# 10_-_FPGA_IO_BANK_3A.net
KiCad netlist of a schematic drawn in Altium Designer
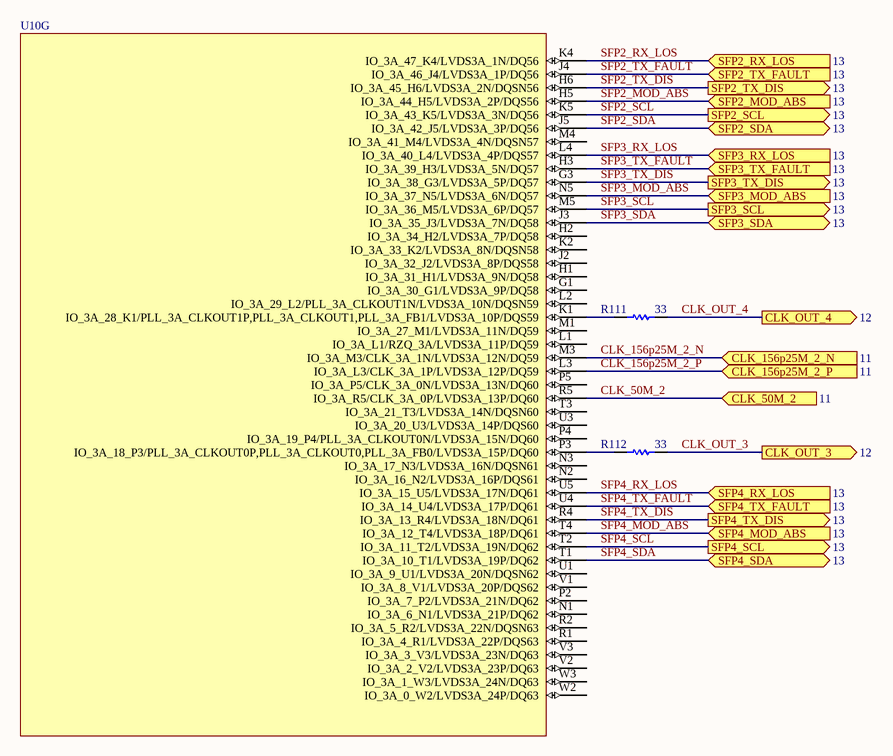
[diagram p0: [10] - FPGA IO BANK 3A.SchDoc]

(export (version "E")
  (design (tool "Eeschema 10.0.6"))
  (components
    (comp (ref "R111")
      (value "33")
      (footprint "0402_R")
      (description "SMD Resistor")
      (fields (field (name "TOLERANCE") "5%"))
      (libsource (lib "Passive Components") (part "Res SMD"))
    )
    (comp (ref "R112")
      (value "33")
      (footprint "0402_R")
      (description "SMD Resistor")
      (fields (field (name "TOLERANCE") "5%"))
      (libsource (lib "Passive Components") (part "Res SMD"))
    )
    (comp (ref "U10")
      (value "10AX016 F27")
      (footprint "FBGA672")
      (libsource (lib "Project_schlib") (part "10AX016"))
    )
  )
  (nets
    (net (code "1") (name "/CLK_50M_2") (class "Default")
      (node (ref "U10") (pin "R5") (pinfunction "IO_3A_R5/CLK_3A_0P/LVDS3A_13P/DQ60_R5") (pintype "bidirectional"))
    )
    (net (code "2") (name "/CLK_156p25M_2_N") (class "Default")
      (node (ref "U10") (pin "M3") (pinfunction "IO_3A_M3/CLK_3A_1N/LVDS3A_12N/DQ59_M3") (pintype "bidirectional"))
    )
    (net (code "3") (name "/CLK_156p25M_2_P") (class "Default")
      (node (ref "U10") (pin "L3") (pinfunction "IO_3A_L3/CLK_3A_1P/LVDS3A_12P/DQ59_L3") (pintype "bidirectional"))
    )
    (net (code "4") (name "/CLK_OUT_3") (class "Default")
      (node (ref "R112") (pin "2") (pinfunction "2_2") (pintype "passive"))
    )
    (net (code "5") (name "/CLK_OUT_4") (class "Default")
      (node (ref "R111") (pin "2") (pinfunction "2_2") (pintype "passive"))
    )
    (net (code "6") (name "/SFP2_MOD_ABS") (class "Default")
      (node (ref "U10") (pin "H5") (pinfunction "IO_3A_44_H5/LVDS3A_2P/DQS56_H5") (pintype "bidirectional"))
    )
    (net (code "7") (name "/SFP2_RX_LOS") (class "Default")
      (node (ref "U10") (pin "K4") (pinfunction "IO_3A_47_K4/LVDS3A_1N/DQ56_K4") (pintype "bidirectional"))
    )
    (net (code "8") (name "/SFP2_SCL") (class "Default")
      (node (ref "U10") (pin "K5") (pinfunction "IO_3A_43_K5/LVDS3A_3N/DQ56_K5") (pintype "bidirectional"))
    )
    (net (code "9") (name "/SFP2_SDA") (class "Default")
      (node (ref "U10") (pin "J5") (pinfunction "IO_3A_42_J5/LVDS3A_3P/DQ56_J5") (pintype "bidirectional"))
    )
    (net (code "10") (name "/SFP2_TX_DIS") (class "Default")
      (node (ref "U10") (pin "H6") (pinfunction "IO_3A_45_H6/LVDS3A_2N/DQSN56_H6") (pintype "bidirectional"))
    )
    (net (code "11") (name "/SFP2_TX_FAULT") (class "Default")
      (node (ref "U10") (pin "J4") (pinfunction "IO_3A_46_J4/LVDS3A_1P/DQ56_J4") (pintype "bidirectional"))
    )
    (net (code "12") (name "/SFP3_MOD_ABS") (class "Default")
      (node (ref "U10") (pin "N5") (pinfunction "IO_3A_37_N5/LVDS3A_6N/DQ57_N5") (pintype "bidirectional"))
    )
    (net (code "13") (name "/SFP3_RX_LOS") (class "Default")
      (node (ref "U10") (pin "L4") (pinfunction "IO_3A_40_L4/LVDS3A_4P/DQS57_L4") (pintype "bidirectional"))
    )
    (net (code "14") (name "/SFP3_SCL") (class "Default")
      (node (ref "U10") (pin "M5") (pinfunction "IO_3A_36_M5/LVDS3A_6P/DQ57_M5") (pintype "bidirectional"))
    )
    (net (code "15") (name "/SFP3_SDA") (class "Default")
      (node (ref "U10") (pin "J3") (pinfunction "IO_3A_35_J3/LVDS3A_7N/DQ58_J3") (pintype "bidirectional"))
    )
    (net (code "16") (name "/SFP3_TX_DIS") (class "Default")
      (node (ref "U10") (pin "G3") (pinfunction "IO_3A_38_G3/LVDS3A_5P/DQ57_G3") (pintype "bidirectional"))
    )
    (net (code "17") (name "/SFP3_TX_FAULT") (class "Default")
      (node (ref "U10") (pin "H3") (pinfunction "IO_3A_39_H3/LVDS3A_5N/DQ57_H3") (pintype "bidirectional"))
    )
    (net (code "18") (name "/SFP4_MOD_ABS") (class "Default")
      (node (ref "U10") (pin "T4") (pinfunction "IO_3A_12_T4/LVDS3A_18P/DQ61_T4") (pintype "bidirectional"))
    )
    (net (code "19") (name "/SFP4_RX_LOS") (class "Default")
      (node (ref "U10") (pin "U5") (pinfunction "IO_3A_15_U5/LVDS3A_17N/DQ61_U5") (pintype "bidirectional"))
    )
    (net (code "20") (name "/SFP4_SCL") (class "Default")
      (node (ref "U10") (pin "T2") (pinfunction "IO_3A_11_T2/LVDS3A_19N/DQ62_T2") (pintype "bidirectional"))
    )
    (net (code "21") (name "/SFP4_SDA") (class "Default")
      (node (ref "U10") (pin "T1") (pinfunction "IO_3A_10_T1/LVDS3A_19P/DQ62_T1") (pintype "bidirectional"))
    )
    (net (code "22") (name "/SFP4_TX_DIS") (class "Default")
      (node (ref "U10") (pin "R4") (pinfunction "IO_3A_13_R4/LVDS3A_18N/DQ61_R4") (pintype "bidirectional"))
    )
    (net (code "23") (name "/SFP4_TX_FAULT") (class "Default")
      (node (ref "U10") (pin "U4") (pinfunction "IO_3A_14_U4/LVDS3A_17P/DQ61_U4") (pintype "bidirectional"))
    )
    (net (code "24") (name "Net-(U10G-IO_3A_18_P3{slash}PLL_3A_CLKOUT0P,PLL_3A_CLKOUT0,PLL_3A_FB0{slash}LVDS3A_15P{slash}DQ60)") (class "Default")
      (node (ref "R112") (pin "1") (pinfunction "1_1") (pintype "passive"))
      (node (ref "U10") (pin "P3") (pinfunction "IO_3A_18_P3/PLL_3A_CLKOUT0P,PLL_3A_CLKOUT0,PLL_3A_FB0/LVDS3A_15P/DQ60_P3") (pintype "bidirectional"))
    )
    (net (code "25") (name "Net-(U10G-IO_3A_28_K1{slash}PLL_3A_CLKOUT1P,PLL_3A_CLKOUT1,PLL_3A_FB1{slash}LVDS3A_10P{slash}DQS59)") (class "Default")
      (node (ref "R111") (pin "1") (pinfunction "1_1") (pintype "passive"))
      (node (ref "U10") (pin "K1") (pinfunction "IO_3A_28_K1/PLL_3A_CLKOUT1P,PLL_3A_CLKOUT1,PLL_3A_FB1/LVDS3A_10P/DQS59_K1") (pintype "bidirectional"))
    )
    (net (code "26") (name "unconnected-(U10G-IO_3A_0_W2{slash}LVDS3A_24P{slash}DQ63-PadW2)") (class "Default")
      (node (ref "U10") (pin "W2") (pinfunction "IO_3A_0_W2/LVDS3A_24P/DQ63_W2") (pintype "bidirectional"))
    )
    (net (code "27") (name "unconnected-(U10G-IO_3A_1_W3{slash}LVDS3A_24N{slash}DQ63-PadW3)") (class "Default")
      (node (ref "U10") (pin "W3") (pinfunction "IO_3A_1_W3/LVDS3A_24N/DQ63_W3") (pintype "bidirectional"))
    )
    (net (code "28") (name "unconnected-(U10G-IO_3A_2_V2{slash}LVDS3A_23P{slash}DQ63-PadV2)") (class "Default")
      (node (ref "U10") (pin "V2") (pinfunction "IO_3A_2_V2/LVDS3A_23P/DQ63_V2") (pintype "bidirectional"))
    )
    (net (code "29") (name "unconnected-(U10G-IO_3A_3_V3{slash}LVDS3A_23N{slash}DQ63-PadV3)") (class "Default")
      (node (ref "U10") (pin "V3") (pinfunction "IO_3A_3_V3/LVDS3A_23N/DQ63_V3") (pintype "bidirectional"))
    )
    (net (code "30") (name "unconnected-(U10G-IO_3A_4_R1{slash}LVDS3A_22P{slash}DQS63-PadR1)") (class "Default")
      (node (ref "U10") (pin "R1") (pinfunction "IO_3A_4_R1/LVDS3A_22P/DQS63_R1") (pintype "bidirectional"))
    )
    (net (code "31") (name "unconnected-(U10G-IO_3A_5_R2{slash}LVDS3A_22N{slash}DQSN63-PadR2)") (class "Default")
      (node (ref "U10") (pin "R2") (pinfunction "IO_3A_5_R2/LVDS3A_22N/DQSN63_R2") (pintype "bidirectional"))
    )
    (net (code "32") (name "unconnected-(U10G-IO_3A_6_N1{slash}LVDS3A_21P{slash}DQ62-PadN1)") (class "Default")
      (node (ref "U10") (pin "N1") (pinfunction "IO_3A_6_N1/LVDS3A_21P/DQ62_N1") (pintype "bidirectional"))
    )
    (net (code "33") (name "unconnected-(U10G-IO_3A_7_P2{slash}LVDS3A_21N{slash}DQ62-PadP2)") (class "Default")
      (node (ref "U10") (pin "P2") (pinfunction "IO_3A_7_P2/LVDS3A_21N/DQ62_P2") (pintype "bidirectional"))
    )
    (net (code "34") (name "unconnected-(U10G-IO_3A_8_V1{slash}LVDS3A_20P{slash}DQS62-PadV1)") (class "Default")
      (node (ref "U10") (pin "V1") (pinfunction "IO_3A_8_V1/LVDS3A_20P/DQS62_V1") (pintype "bidirectional"))
    )
    (net (code "35") (name "unconnected-(U10G-IO_3A_9_U1{slash}LVDS3A_20N{slash}DQSN62-PadU1)") (class "Default")
      (node (ref "U10") (pin "U1") (pinfunction "IO_3A_9_U1/LVDS3A_20N/DQSN62_U1") (pintype "bidirectional"))
    )
    (net (code "36") (name "unconnected-(U10G-IO_3A_16_N2{slash}LVDS3A_16P{slash}DQS61-PadN2)") (class "Default")
      (node (ref "U10") (pin "N2") (pinfunction "IO_3A_16_N2/LVDS3A_16P/DQS61_N2") (pintype "bidirectional"))
    )
    (net (code "37") (name "unconnected-(U10G-IO_3A_17_N3{slash}LVDS3A_16N{slash}DQSN61-PadN3)") (class "Default")
      (node (ref "U10") (pin "N3") (pinfunction "IO_3A_17_N3/LVDS3A_16N/DQSN61_N3") (pintype "bidirectional"))
    )
    (net (code "38") (name "unconnected-(U10G-IO_3A_19_P4{slash}PLL_3A_CLKOUT0N{slash}LVDS3A_15N{slash}DQ60-PadP4)") (class "Default")
      (node (ref "U10") (pin "P4") (pinfunction "IO_3A_19_P4/PLL_3A_CLKOUT0N/LVDS3A_15N/DQ60_P4") (pintype "bidirectional"))
    )
    (net (code "39") (name "unconnected-(U10G-IO_3A_20_U3{slash}LVDS3A_14P{slash}DQS60-PadU3)") (class "Default")
      (node (ref "U10") (pin "U3") (pinfunction "IO_3A_20_U3/LVDS3A_14P/DQS60_U3") (pintype "bidirectional"))
    )
    (net (code "40") (name "unconnected-(U10G-IO_3A_21_T3{slash}LVDS3A_14N{slash}DQSN60-PadT3)") (class "Default")
      (node (ref "U10") (pin "T3") (pinfunction "IO_3A_21_T3/LVDS3A_14N/DQSN60_T3") (pintype "bidirectional"))
    )
    (net (code "41") (name "unconnected-(U10G-IO_3A_27_M1{slash}LVDS3A_11N{slash}DQ59-PadM1)") (class "Default")
      (node (ref "U10") (pin "M1") (pinfunction "IO_3A_27_M1/LVDS3A_11N/DQ59_M1") (pintype "bidirectional"))
    )
    (net (code "42") (name "unconnected-(U10G-IO_3A_29_L2{slash}PLL_3A_CLKOUT1N{slash}LVDS3A_10N{slash}DQSN59-PadL2)") (class "Default")
      (node (ref "U10") (pin "L2") (pinfunction "IO_3A_29_L2/PLL_3A_CLKOUT1N/LVDS3A_10N/DQSN59_L2") (pintype "bidirectional"))
    )
    (net (code "43") (name "unconnected-(U10G-IO_3A_30_G1{slash}LVDS3A_9P{slash}DQ58-PadG1)") (class "Default")
      (node (ref "U10") (pin "G1") (pinfunction "IO_3A_30_G1/LVDS3A_9P/DQ58_G1") (pintype "bidirectional"))
    )
    (net (code "44") (name "unconnected-(U10G-IO_3A_31_H1{slash}LVDS3A_9N{slash}DQ58-PadH1)") (class "Default")
      (node (ref "U10") (pin "H1") (pinfunction "IO_3A_31_H1/LVDS3A_9N/DQ58_H1") (pintype "bidirectional"))
    )
    (net (code "45") (name "unconnected-(U10G-IO_3A_32_J2{slash}LVDS3A_8P{slash}DQS58-PadJ2)") (class "Default")
      (node (ref "U10") (pin "J2") (pinfunction "IO_3A_32_J2/LVDS3A_8P/DQS58_J2") (pintype "bidirectional"))
    )
    (net (code "46") (name "unconnected-(U10G-IO_3A_33_K2{slash}LVDS3A_8N{slash}DQSN58-PadK2)") (class "Default")
      (node (ref "U10") (pin "K2") (pinfunction "IO_3A_33_K2/LVDS3A_8N/DQSN58_K2") (pintype "bidirectional"))
    )
    (net (code "47") (name "unconnected-(U10G-IO_3A_34_H2{slash}LVDS3A_7P{slash}DQ58-PadH2)") (class "Default")
      (node (ref "U10") (pin "H2") (pinfunction "IO_3A_34_H2/LVDS3A_7P/DQ58_H2") (pintype "bidirectional"))
    )
    (net (code "48") (name "unconnected-(U10G-IO_3A_41_M4{slash}LVDS3A_4N{slash}DQSN57-PadM4)") (class "Default")
      (node (ref "U10") (pin "M4") (pinfunction "IO_3A_41_M4/LVDS3A_4N/DQSN57_M4") (pintype "bidirectional"))
    )
    (net (code "49") (name "unconnected-(U10G-IO_3A_L1{slash}RZQ_3A{slash}LVDS3A_11P{slash}DQ59-PadL1)") (class "Default")
      (node (ref "U10") (pin "L1") (pinfunction "IO_3A_L1/RZQ_3A/LVDS3A_11P/DQ59_L1") (pintype "bidirectional"))
    )
    (net (code "50") (name "unconnected-(U10G-IO_3A_P5{slash}CLK_3A_0N{slash}LVDS3A_13N{slash}DQ60-PadP5)") (class "Default")
      (node (ref "U10") (pin "P5") (pinfunction "IO_3A_P5/CLK_3A_0N/LVDS3A_13N/DQ60_P5") (pintype "bidirectional"))
    )
  )
)
